# 03_-PYTHON500_INTERFACE.net
KiCad netlist of a schematic drawn in Altium Designer
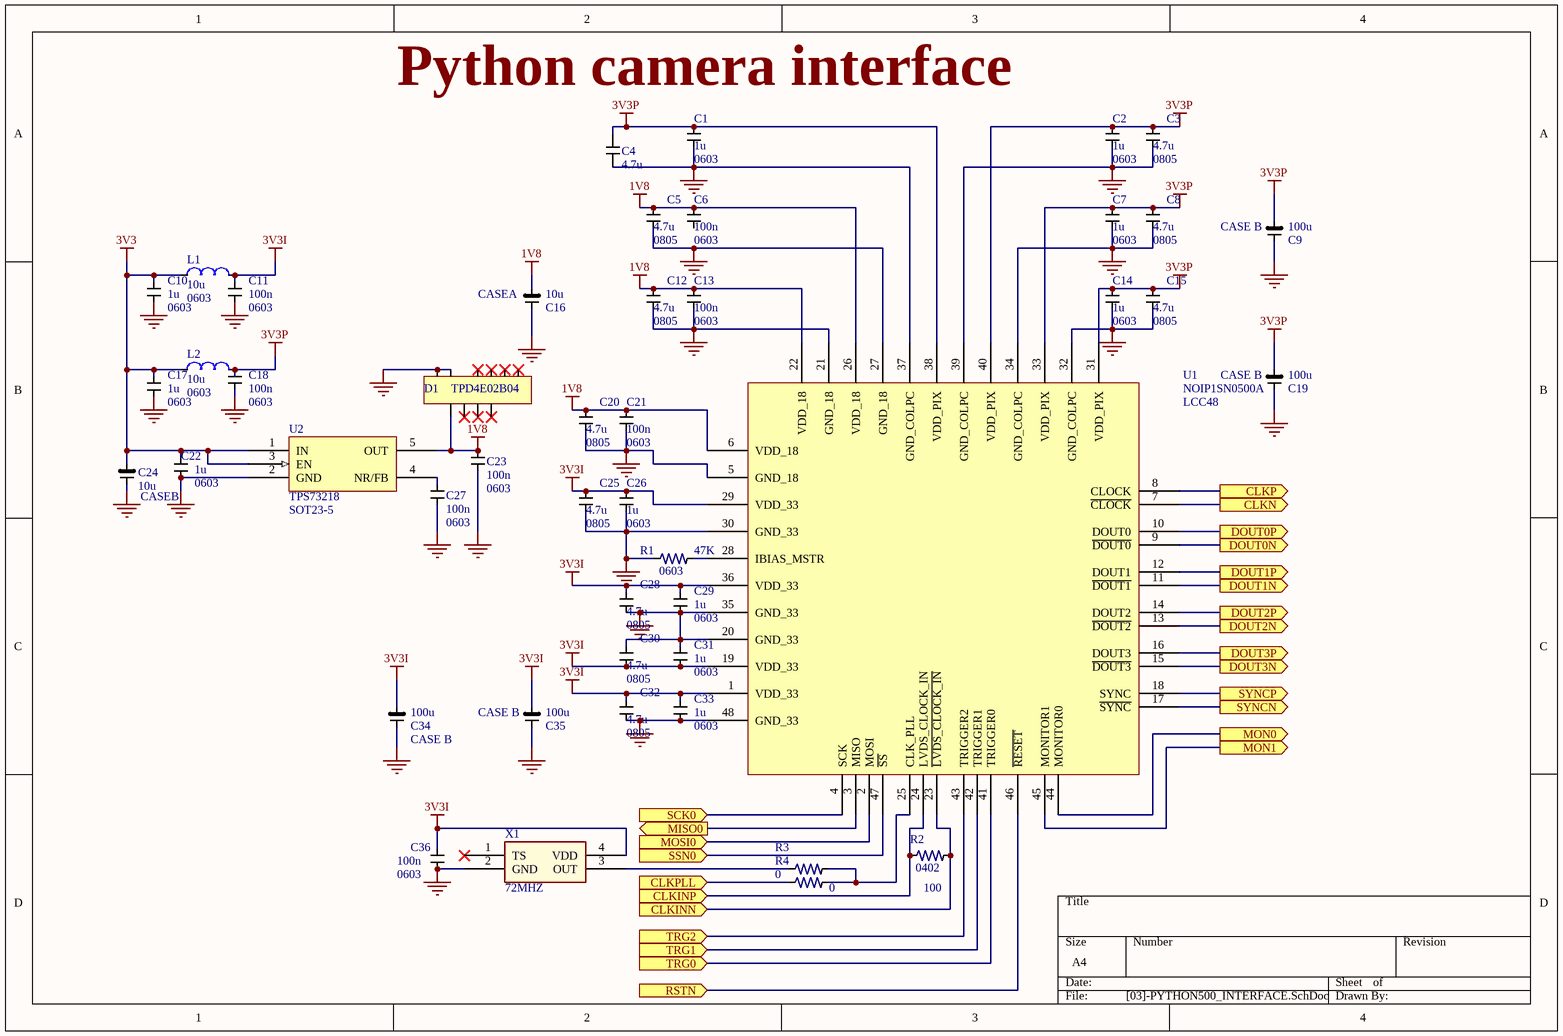
[diagram p0: [03]-PYTHON500_INTERFACE.SchDoc]

(export (version "E")
  (design (tool "Eeschema 10.0.6"))
  (components
    (comp (ref "C1")
      (value "1u")
      (footprint "*0603")
      (fields (field (name "PCB LAYER:") "0603"))
      (libsource (lib "0603YC105KAT2A") (part "Component_1"))
    )
    (comp (ref "C2")
      (value "1u")
      (footprint "*0603")
      (fields (field (name "PCB LAYER:") "0603"))
      (libsource (lib "0603YC105KAT2A") (part "Component_1"))
    )
    (comp (ref "C3")
      (value "4.7u")
      (footprint "*CAPC2013X140N")
      (fields (field (name "PCB PACKAGE") "0805"))
      (libsource (lib "08053D475KAT2A") (part "Component_1"))
    )
    (comp (ref "C4") (value "4.7u") (footprint "*CAPC2013X140N") (libsource (lib "") (part "Component_1_1")))
    (comp (ref "C5")
      (value "4.7u")
      (footprint "*CAPC2013X140N")
      (fields (field (name "PCB PACKAGE") "0805"))
      (libsource (lib "08053D475KAT2A") (part "Component_1"))
    )
    (comp (ref "C6")
      (value "100n")
      (fields (field (name "PCB FOOTPRINT") "0603"))
      (libsource (lib "06031C104KAT2A") (part "Component_1"))
    )
    (comp (ref "C7")
      (value "1u")
      (footprint "*0603")
      (fields (field (name "PCB LAYER:") "0603"))
      (libsource (lib "0603YC105KAT2A") (part "Component_1"))
    )
    (comp (ref "C8")
      (value "4.7u")
      (footprint "*CAPC2013X140N")
      (fields (field (name "PCB PACKAGE") "0805"))
      (libsource (lib "08053D475KAT2A") (part "Component_1"))
    )
    (comp (ref "C9")
      (value "100u")
      (footprint "CAPC3529X21N")
      (fields (field (name "CASE") "CASE B"))
      (libsource (lib "TAJB107K006TNJ") (part "Component_1"))
    )
    (comp (ref "C10")
      (value "1u")
      (fields (field (name "PCB SIZE") "0603"))
      (libsource (lib "0402ZD105KAT2A") (part "Component_1"))
    )
    (comp (ref "C11")
      (value "100n")
      (fields (field (name "PCB FOOTPRINT") "0603"))
      (libsource (lib "06031C104KAT2A") (part "Component_1"))
    )
    (comp (ref "C12")
      (value "4.7u")
      (footprint "*CAPC2013X140N")
      (fields (field (name "PCB PACKAGE") "0805"))
      (libsource (lib "08053D475KAT2A") (part "Component_1"))
    )
    (comp (ref "C13")
      (value "100n")
      (fields (field (name "PCB FOOTPRINT") "0603"))
      (libsource (lib "06031C104KAT2A") (part "Component_1"))
    )
    (comp (ref "C14")
      (value "1u")
      (footprint "*0603")
      (fields (field (name "PCB LAYER:") "0603"))
      (libsource (lib "0603YC105KAT2A") (part "Component_1"))
    )
    (comp (ref "C15")
      (value "4.7u")
      (footprint "*CAPC2013X140N")
      (fields (field (name "PCB PACKAGE") "0805"))
      (libsource (lib "08053D475KAT2A") (part "Component_1"))
    )
    (comp (ref "C16")
      (value "10u")
      (footprint "CAPCP3216X18N")
      (fields (field (name "CASE TYPE:") "CASEA"))
      (libsource (lib "T491A106M004AT") (part "Component_1"))
    )
    (comp (ref "C17")
      (value "1u")
      (fields (field (name "PCB SIZE") "0603"))
      (libsource (lib "0402ZD105KAT2A") (part "Component_1"))
    )
    (comp (ref "C18")
      (value "100n")
      (fields (field (name "PCB FOOTPRINT") "0603"))
      (libsource (lib "06031C104KAT2A") (part "Component_1"))
    )
    (comp (ref "C19")
      (value "100u")
      (footprint "CAPC3529X21N")
      (fields (field (name "CASE") "CASE B"))
      (libsource (lib "TAJB107K006TNJ") (part "Component_1"))
    )
    (comp (ref "C20")
      (value "4.7u")
      (footprint "*CAPC2013X140N")
      (fields (field (name "PCB PACKAGE") "0805"))
      (libsource (lib "08053D475KAT2A") (part "Component_1"))
    )
    (comp (ref "C21")
      (value "100n")
      (fields (field (name "PCB FOOTPRINT") "0603"))
      (libsource (lib "06031C104KAT2A") (part "Component_1"))
    )
    (comp (ref "C22")
      (value "1u")
      (footprint "*0603")
      (fields (field (name "PCB LAYER:") "0603"))
      (libsource (lib "0603YC105KAT2A") (part "Component_1"))
    )
    (comp (ref "C23")
      (value "100n")
      (fields (field (name "PCB FOOTPRINT") "0603"))
      (libsource (lib "06031C104KAT2A") (part "Component_1"))
    )
    (comp (ref "C24")
      (value "10u")
      (footprint "CAPC3528X21N")
      (fields (field (name "PCB LAYER") "CASEB"))
      (libsource (lib "T495B106K010ATE600") (part "Component_1"))
    )
    (comp (ref "C25")
      (value "4.7u")
      (footprint "*CAPC2013X140N")
      (fields (field (name "PCB PACKAGE") "0805"))
      (libsource (lib "08053D475KAT2A") (part "Component_1"))
    )
    (comp (ref "C26")
      (value "1u")
      (footprint "*0603")
      (fields (field (name "PCB LAYER:") "0603"))
      (libsource (lib "0603YC105KAT2A") (part "Component_1"))
    )
    (comp (ref "C27")
      (value "100n")
      (fields (field (name "PCB FOOTPRINT") "0603"))
      (libsource (lib "06031C104KAT2A") (part "Component_1"))
    )
    (comp (ref "C28")
      (value "4.7u")
      (footprint "*CAPC2013X140N")
      (fields (field (name "PCB PACKAGE") "0805"))
      (libsource (lib "08053D475KAT2A") (part "Component_1"))
    )
    (comp (ref "C29")
      (value "1u")
      (fields (field (name "PCB SIZE") "0603"))
      (libsource (lib "0402ZD105KAT2A") (part "Component_1"))
    )
    (comp (ref "C30")
      (value "4.7u")
      (footprint "*CAPC2013X140N")
      (fields (field (name "PCB PACKAGE") "0805"))
      (libsource (lib "08053D475KAT2A") (part "Component_1"))
    )
    (comp (ref "C31")
      (value "1u")
      (fields (field (name "PCB SIZE") "0603"))
      (libsource (lib "0402ZD105KAT2A") (part "Component_1"))
    )
    (comp (ref "C32")
      (value "4.7u")
      (footprint "*CAPC2013X140N")
      (fields (field (name "PCB PACKAGE") "0805"))
      (libsource (lib "08053D475KAT2A") (part "Component_1"))
    )
    (comp (ref "C33")
      (value "1u")
      (fields (field (name "PCB SIZE") "0603"))
      (libsource (lib "0402ZD105KAT2A") (part "Component_1"))
    )
    (comp (ref "C34")
      (value "100u")
      (footprint "CAPC3529X21N")
      (fields (field (name "CASE") "CASE B"))
      (libsource (lib "TAJB107K006TNJ") (part "Component_1"))
    )
    (comp (ref "C35")
      (value "100u")
      (footprint "CAPC3529X21N")
      (fields (field (name "CASE") "CASE B"))
      (libsource (lib "TAJB107K006TNJ") (part "Component_1"))
    )
    (comp (ref "C36")
      (value "100n")
      (fields (field (name "PCB FOOTPRINT") "0603"))
      (libsource (lib "06031C104KAT2A") (part "Component_1"))
    )
    (comp (ref "D1")
      (value "TPD4E02B04")
      (footprint "TI_TPD4E05U06DQAR")
      (libsource (lib "TPD4E02B04") (part "Component_1"))
    )
    (comp (ref "L1")
      (value "10u")
      (footprint "*INDC1608X95N")
      (fields (field (name "PCB LAYOUT:") "0603"))
      (libsource (lib "MLZ1608M100WTD25") (part "Component_1"))
    )
    (comp (ref "L2")
      (value "10u")
      (footprint "*INDC1608X95N")
      (fields (field (name "PCB LAYOUT:") "0603"))
      (libsource (lib "MLZ1608M100WTD25") (part "Component_1"))
    )
    (comp (ref "R1")
      (value "47K")
      (footprint "*0603")
      (description "Res Thin Film 0603 76.8 Ohm 0.1% 1/10W Â±15ppm/Â°C Molded SMD Paper T/R")
      (fields
        (field (name "MP") "RP73D1J76R8BTDG")
        (field (name "MF") "TE Connectivity / Holsworthy")
        (field (name "FOOT PRINT") "0603")
      )
      (libsource (lib "CRCW060347K0FKEA") (part "RP73D1J76R8BTDG"))
    )
    (comp (ref "R2")
      (value "100")
      (footprint "*RESC1608X50N")
      (description "Res Thin Film 0603 76.8 Ohm 0.1% 1/10W Â±15ppm/Â°C Molded SMD Paper T/R")
      (fields
        (field (name "MP") "RP73D1J76R8BTDG")
        (field (name "MF") "TE Connectivity / Holsworthy")
        (field (name "FOOT PRINT") "0402")
      )
      (libsource (lib "CRGH0603F4K7") (part "RP73D1J76R8BTDG"))
    )
    (comp (ref "R3")
      (value "0")
      (footprint "*0603")
      (description "Res Thin Film 0603 76.8 Ohm 0.1% 1/10W Â±15ppm/Â°C Molded SMD Paper T/R")
      (fields (field (name "MP") "RP73D1J76R8BTDG") (field (name "MF") "TE Connectivity / Holsworthy"))
      (libsource (lib "CRCW06030000Z0EA") (part "RP73D1J76R8BTDG"))
    )
    (comp (ref "R4")
      (value "0")
      (footprint "*0603")
      (description "Res Thin Film 0603 76.8 Ohm 0.1% 1/10W Â±15ppm/Â°C Molded SMD Paper T/R")
      (fields (field (name "MP") "RP73D1J76R8BTDG") (field (name "MF") "TE Connectivity / Holsworthy"))
      (libsource (lib "CRCW06030000Z0EA") (part "RP73D1J76R8BTDG"))
    )
    (comp (ref "U1")
      (value "NOIP1SN0500A")
      (footprint "LCC101P1430X1430X228-48N")
      (description "Python camera sensor. Having pixel output of 500 by 600.")
      (fields
        (field (name "PART NO.") "NOIP1SN0500A-QDI")
        (field (name "PACKAGE TYPE") "LCC48")
        (field (name "DESIGNER") "Faheem")
      )
      (libsource (lib "NOIP1SN0500A") (part "Component_1"))
    )
    (comp (ref "U2")
      (value "TPS73218")
      (footprint "*SOT95P280X145-5N")
      (fields (field (name "PCB FOOTPRINT TYPE:") "SOT23-5"))
      (libsource (lib "TPS73218DBVT") (part "Component_1"))
    )
    (comp (ref "X1")
      (value "72MHZ")
      (footprint "OSCSC320X250X100N")
      (fields (field (name "MF_PART NO.") "ASFLMB-72.000MHZ-XY-T"))
      (libsource (lib "ASFLMB-72.000MHZ-XY-T") (part "Component_1"))
    )
  )
  (nets
    (net (code "1") (name "/CLKINN") (class "Default")
      (node (ref "R2") (pin "2") (pinfunction "2_2") (pintype "passive"))
      (node (ref "U1") (pin "23") (pinfunction "~{LVDS_CLOCK_IN}_23") (pintype "passive"))
    )
    (net (code "2") (name "/CLKINP") (class "Default")
      (node (ref "R2") (pin "1") (pinfunction "1_1") (pintype "passive"))
      (node (ref "U1") (pin "24") (pinfunction "LVDS_CLOCK_IN_24") (pintype "passive"))
    )
    (net (code "3") (name "/CLKN") (class "Default")
      (node (ref "U1") (pin "7") (pinfunction "~{CLOCK}_7") (pintype "passive"))
    )
    (net (code "4") (name "/CLKP") (class "Default")
      (node (ref "U1") (pin "8") (pinfunction "CLOCK_8") (pintype "passive"))
    )
    (net (code "5") (name "/CLKPLL") (class "Default")
      (node (ref "R4") (pin "1") (pinfunction "1_1") (pintype "passive"))
    )
    (net (code "6") (name "/DOUT0N") (class "Default")
      (node (ref "U1") (pin "9") (pinfunction "~{DOUT0}_9") (pintype "passive"))
    )
    (net (code "7") (name "/DOUT0P") (class "Default")
      (node (ref "U1") (pin "10") (pinfunction "DOUT0_10") (pintype "passive"))
    )
    (net (code "8") (name "/DOUT1N") (class "Default")
      (node (ref "U1") (pin "11") (pinfunction "~{DOUT1}_11") (pintype "passive"))
    )
    (net (code "9") (name "/DOUT1P") (class "Default")
      (node (ref "U1") (pin "12") (pinfunction "DOUT1_12") (pintype "passive"))
    )
    (net (code "10") (name "/DOUT2N") (class "Default")
      (node (ref "U1") (pin "13") (pinfunction "~{DOUT2}_13") (pintype "passive"))
    )
    (net (code "11") (name "/DOUT2P") (class "Default")
      (node (ref "U1") (pin "14") (pinfunction "DOUT2_14") (pintype "passive"))
    )
    (net (code "12") (name "/DOUT3N") (class "Default")
      (node (ref "U1") (pin "15") (pinfunction "~{DOUT3}_15") (pintype "passive"))
    )
    (net (code "13") (name "/DOUT3P") (class "Default")
      (node (ref "U1") (pin "16") (pinfunction "DOUT3_16") (pintype "passive"))
    )
    (net (code "14") (name "/MISO0") (class "Default")
      (node (ref "U1") (pin "3") (pinfunction "MISO_3") (pintype "passive"))
    )
    (net (code "15") (name "/MON0") (class "Default")
      (node (ref "U1") (pin "44") (pinfunction "MONITOR0_44") (pintype "passive"))
    )
    (net (code "16") (name "/MON1") (class "Default")
      (node (ref "U1") (pin "45") (pinfunction "MONITOR1_45") (pintype "passive"))
    )
    (net (code "17") (name "/MOSI0") (class "Default")
      (node (ref "U1") (pin "2") (pinfunction "MOSI_2") (pintype "passive"))
    )
    (net (code "18") (name "/RSTN") (class "Default")
      (node (ref "U1") (pin "46") (pinfunction "~{RESET}_46") (pintype "passive"))
    )
    (net (code "19") (name "/SCK0") (class "Default")
      (node (ref "U1") (pin "4") (pinfunction "SCK_4") (pintype "passive"))
    )
    (net (code "20") (name "/SSN0") (class "Default")
      (node (ref "U1") (pin "47") (pinfunction "~{SS}_47") (pintype "passive"))
    )
    (net (code "21") (name "/SYNCN") (class "Default")
      (node (ref "U1") (pin "17") (pinfunction "~{SYNC}_17") (pintype "passive"))
    )
    (net (code "22") (name "/SYNCP") (class "Default")
      (node (ref "U1") (pin "18") (pinfunction "SYNC_18") (pintype "passive"))
    )
    (net (code "23") (name "/TRG0") (class "Default")
      (node (ref "U1") (pin "41") (pinfunction "TRIGGER0_41") (pintype "passive"))
    )
    (net (code "24") (name "/TRG1") (class "Default")
      (node (ref "U1") (pin "42") (pinfunction "TRIGGER1_42") (pintype "passive"))
    )
    (net (code "25") (name "/TRG2") (class "Default")
      (node (ref "U1") (pin "43") (pinfunction "TRIGGER2_43") (pintype "passive"))
    )
    (net (code "26") (name "1V8") (class "Default")
      (node (ref "C12") (pin "2") (pinfunction "2_2") (pintype "passive"))
      (node (ref "C13") (pin "2") (pinfunction "2_2") (pintype "passive"))
      (node (ref "C16") (pin "1") (pinfunction "1_1") (pintype "passive"))
      (node (ref "C20") (pin "2") (pinfunction "2_2") (pintype "passive"))
      (node (ref "C21") (pin "2") (pinfunction "2_2") (pintype "passive"))
      (node (ref "C23") (pin "2") (pinfunction "2_2") (pintype "passive"))
      (node (ref "C5") (pin "2") (pinfunction "2_2") (pintype "passive"))
      (node (ref "C6") (pin "2") (pinfunction "2_2") (pintype "passive"))
      (node (ref "D1") (pin "1") (pinfunction "IO1_1") (pintype "passive"))
      (node (ref "U1") (pin "22") (pinfunction "VDD_18_22") (pintype "power_in"))
      (node (ref "U1") (pin "26") (pinfunction "VDD_18_26") (pintype "power_in"))
      (node (ref "U1") (pin "6") (pinfunction "VDD_18_6") (pintype "power_in"))
      (node (ref "U2") (pin "5") (pinfunction "OUT_5") (pintype "power_in"))
    )
    (net (code "27") (name "3V3") (class "Default")
      (node (ref "C10") (pin "2") (pinfunction "2_2") (pintype "passive"))
      (node (ref "C17") (pin "2") (pinfunction "2_2") (pintype "passive"))
      (node (ref "C22") (pin "2") (pinfunction "2_2") (pintype "passive"))
      (node (ref "C24") (pin "1") (pinfunction "1_1") (pintype "passive"))
      (node (ref "L1") (pin "1") (pinfunction "1_1") (pintype "passive"))
      (node (ref "L2") (pin "1") (pinfunction "1_1") (pintype "passive"))
      (node (ref "U2") (pin "1") (pinfunction "IN_1") (pintype "power_in"))
      (node (ref "U2") (pin "3") (pinfunction "EN_3") (pintype "input"))
    )
    (net (code "28") (name "3V3I") (class "Default")
      (node (ref "C11") (pin "2") (pinfunction "2_2") (pintype "passive"))
      (node (ref "C25") (pin "2") (pinfunction "2_2") (pintype "passive"))
      (node (ref "C26") (pin "2") (pinfunction "2_2") (pintype "passive"))
      (node (ref "C28") (pin "2") (pinfunction "2_2") (pintype "passive"))
      (node (ref "C29") (pin "2") (pinfunction "2_2") (pintype "passive"))
      (node (ref "C30") (pin "1") (pinfunction "1_1") (pintype "passive"))
      (node (ref "C31") (pin "1") (pinfunction "1_1") (pintype "passive"))
      (node (ref "C32") (pin "2") (pinfunction "2_2") (pintype "passive"))
      (node (ref "C33") (pin "2") (pinfunction "2_2") (pintype "passive"))
      (node (ref "C34") (pin "1") (pinfunction "1_1") (pintype "passive"))
      (node (ref "C35") (pin "1") (pinfunction "1_1") (pintype "passive"))
      (node (ref "C36") (pin "2") (pinfunction "2_2") (pintype "passive"))
      (node (ref "L1") (pin "2") (pinfunction "2_2") (pintype "passive"))
      (node (ref "U1") (pin "1") (pinfunction "VDD_33_1") (pintype "power_in"))
      (node (ref "U1") (pin "19") (pinfunction "VDD_33_19") (pintype "power_in"))
      (node (ref "U1") (pin "29") (pinfunction "VDD_33_29") (pintype "power_in"))
      (node (ref "U1") (pin "36") (pinfunction "VDD_33_36") (pintype "power_in"))
      (node (ref "X1") (pin "4") (pinfunction "VDD_4") (pintype "passive"))
    )
    (net (code "29") (name "3V3P") (class "Default")
      (node (ref "C1") (pin "2") (pinfunction "2_2") (pintype "passive"))
      (node (ref "C14") (pin "2") (pinfunction "2_2") (pintype "passive"))
      (node (ref "C15") (pin "2") (pinfunction "2_2") (pintype "passive"))
      (node (ref "C18") (pin "2") (pinfunction "2_2") (pintype "passive"))
      (node (ref "C19") (pin "1") (pinfunction "1_1") (pintype "passive"))
      (node (ref "C2") (pin "2") (pinfunction "2_2") (pintype "passive"))
      (node (ref "C3") (pin "2") (pinfunction "2_2") (pintype "passive"))
      (node (ref "C4") (pin "1") (pinfunction "1_1") (pintype "passive"))
      (node (ref "C7") (pin "2") (pinfunction "2_2") (pintype "passive"))
      (node (ref "C8") (pin "2") (pinfunction "2_2") (pintype "passive"))
      (node (ref "C9") (pin "1") (pinfunction "1_1") (pintype "passive"))
      (node (ref "L2") (pin "2") (pinfunction "2_2") (pintype "passive"))
      (node (ref "U1") (pin "31") (pinfunction "VDD_PIX_31") (pintype "power_in"))
      (node (ref "U1") (pin "33") (pinfunction "VDD_PIX_33") (pintype "power_in"))
      (node (ref "U1") (pin "38") (pinfunction "VDD_PIX_38") (pintype "power_in"))
      (node (ref "U1") (pin "40") (pinfunction "VDD_PIX_40") (pintype "power_in"))
    )
    (net (code "30") (name "GND") (class "Default")
      (node (ref "C1") (pin "1") (pinfunction "1_1") (pintype "passive"))
      (node (ref "C10") (pin "1") (pinfunction "1_1") (pintype "passive"))
      (node (ref "C11") (pin "1") (pinfunction "1_1") (pintype "passive"))
      (node (ref "C12") (pin "1") (pinfunction "1_1") (pintype "passive"))
      (node (ref "C13") (pin "1") (pinfunction "1_1") (pintype "passive"))
      (node (ref "C14") (pin "1") (pinfunction "1_1") (pintype "passive"))
      (node (ref "C15") (pin "1") (pinfunction "1_1") (pintype "passive"))
      (node (ref "C16") (pin "2") (pinfunction "2_2") (pintype "passive"))
      (node (ref "C17") (pin "1") (pinfunction "1_1") (pintype "passive"))
      (node (ref "C18") (pin "1") (pinfunction "1_1") (pintype "passive"))
      (node (ref "C19") (pin "2") (pinfunction "2_2") (pintype "passive"))
      (node (ref "C2") (pin "1") (pinfunction "1_1") (pintype "passive"))
      (node (ref "C20") (pin "1") (pinfunction "1_1") (pintype "passive"))
      (node (ref "C21") (pin "1") (pinfunction "1_1") (pintype "passive"))
      (node (ref "C22") (pin "1") (pinfunction "1_1") (pintype "passive"))
      (node (ref "C23") (pin "1") (pinfunction "1_1") (pintype "passive"))
      (node (ref "C24") (pin "2") (pinfunction "2_2") (pintype "passive"))
      (node (ref "C25") (pin "1") (pinfunction "1_1") (pintype "passive"))
      (node (ref "C26") (pin "1") (pinfunction "1_1") (pintype "passive"))
      (node (ref "C27") (pin "1") (pinfunction "1_1") (pintype "passive"))
      (node (ref "C28") (pin "1") (pinfunction "1_1") (pintype "passive"))
      (node (ref "C29") (pin "1") (pinfunction "1_1") (pintype "passive"))
      (node (ref "C3") (pin "1") (pinfunction "1_1") (pintype "passive"))
      (node (ref "C30") (pin "2") (pinfunction "2_2") (pintype "passive"))
      (node (ref "C31") (pin "2") (pinfunction "2_2") (pintype "passive"))
      (node (ref "C32") (pin "1") (pinfunction "1_1") (pintype "passive"))
      (node (ref "C33") (pin "1") (pinfunction "1_1") (pintype "passive"))
      (node (ref "C34") (pin "2") (pinfunction "2_2") (pintype "passive"))
      (node (ref "C35") (pin "2") (pinfunction "2_2") (pintype "passive"))
      (node (ref "C36") (pin "1") (pinfunction "1_1") (pintype "passive"))
      (node (ref "C4") (pin "2") (pinfunction "2_2") (pintype "passive"))
      (node (ref "C5") (pin "1") (pinfunction "1_1") (pintype "passive"))
      (node (ref "C7") (pin "1") (pinfunction "1_1") (pintype "passive"))
      (node (ref "C8") (pin "1") (pinfunction "1_1") (pintype "passive"))
      (node (ref "C9") (pin "2") (pinfunction "2_2") (pintype "passive"))
      (node (ref "D1") (pin "3") (pinfunction "GND_3") (pintype "power_in"))
      (node (ref "D1") (pin "8") (pinfunction "GND_8") (pintype "power_in"))
      (node (ref "R1") (pin "1") (pinfunction "1_1") (pintype "passive"))
      (node (ref "U1") (pin "20") (pinfunction "GND_33_20") (pintype "power_in"))
      (node (ref "U1") (pin "21") (pinfunction "GND_18_21") (pintype "power_in"))
      (node (ref "U1") (pin "27") (pinfunction "GND_18_27") (pintype "power_in"))
      (node (ref "U1") (pin "30") (pinfunction "GND_33_30") (pintype "power_in"))
      (node (ref "U1") (pin "32") (pinfunction "GND_COLPC_32") (pintype "power_in"))
      (node (ref "U1") (pin "34") (pinfunction "GND_COLPC_34") (pintype "power_in"))
      (node (ref "U1") (pin "35") (pinfunction "GND_33_35") (pintype "power_in"))
      (node (ref "U1") (pin "37") (pinfunction "GND_COLPC_37") (pintype "power_in"))
      (node (ref "U1") (pin "39") (pinfunction "GND_COLPC_39") (pintype "power_in"))
      (node (ref "U1") (pin "48") (pinfunction "GND_33_48") (pintype "power_in"))
      (node (ref "U1") (pin "5") (pinfunction "GND_18_5") (pintype "power_in"))
      (node (ref "U2") (pin "2") (pinfunction "GND_2") (pintype "power_in"))
      (node (ref "X1") (pin "2") (pinfunction "GND_2") (pintype "passive"))
    )
    (net (code "31") (name "Net-(U1-CLK_PLL)") (class "Default")
      (node (ref "R3") (pin "2") (pinfunction "2_2") (pintype "passive"))
      (node (ref "R4") (pin "2") (pinfunction "2_2") (pintype "passive"))
      (node (ref "U1") (pin "25") (pinfunction "CLK_PLL_25") (pintype "passive"))
    )
    (net (code "32") (name "Net-(U1-IBIAS_MSTR)") (class "Default")
      (node (ref "R1") (pin "2") (pinfunction "2_2") (pintype "passive"))
      (node (ref "U1") (pin "28") (pinfunction "IBIAS_MSTR_28") (pintype "passive"))
    )
    (net (code "33") (name "Net-(U2-NR{slash}FB)") (class "Default")
      (node (ref "C27") (pin "2") (pinfunction "2_2") (pintype "passive"))
      (node (ref "U2") (pin "4") (pinfunction "NR/FB_4") (pintype "open_emitter"))
    )
    (net (code "34") (name "Net-(X1-OUT)") (class "Default")
      (node (ref "R3") (pin "1") (pinfunction "1_1") (pintype "passive"))
      (node (ref "X1") (pin "3") (pinfunction "OUT_3") (pintype "passive"))
    )
    (net (code "35") (name "unconnected-(C6-Pad1)") (class "Default")
      (node (ref "C6") (pin "1") (pinfunction "1_1") (pintype "passive"))
    )
    (net (code "36") (name "unconnected-(D1-IO2-Pad2)") (class "Default")
      (node (ref "D1") (pin "2") (pinfunction "IO2_2") (pintype "passive+no_connect"))
    )
    (net (code "37") (name "unconnected-(D1-IO3-Pad4)") (class "Default")
      (node (ref "D1") (pin "4") (pinfunction "IO3_4") (pintype "passive+no_connect"))
    )
    (net (code "38") (name "unconnected-(D1-IO4-Pad5)") (class "Default")
      (node (ref "D1") (pin "5") (pinfunction "IO4_5") (pintype "passive+no_connect"))
    )
    (net (code "39") (name "unconnected-(D1-NC-Pad6)") (class "Default")
      (node (ref "D1") (pin "6") (pinfunction "NC_6") (pintype "open_emitter+no_connect"))
    )
    (net (code "40") (name "unconnected-(D1-NC-Pad7)") (class "Default")
      (node (ref "D1") (pin "7") (pinfunction "NC_7") (pintype "open_emitter+no_connect"))
    )
    (net (code "41") (name "unconnected-(D1-NC-Pad9)") (class "Default")
      (node (ref "D1") (pin "9") (pinfunction "NC_9") (pintype "open_emitter+no_connect"))
    )
    (net (code "42") (name "unconnected-(D1-NC-Pad10)") (class "Default")
      (node (ref "D1") (pin "10") (pinfunction "NC_10") (pintype "open_emitter+no_connect"))
    )
    (net (code "43") (name "unconnected-(X1-TS-Pad1)") (class "Default")
      (node (ref "X1") (pin "1") (pinfunction "TS_1") (pintype "passive+no_connect"))
    )
  )
)
